# AnimatronicMouth.net
KiCad netlist of a schematic drawn in EAGLE
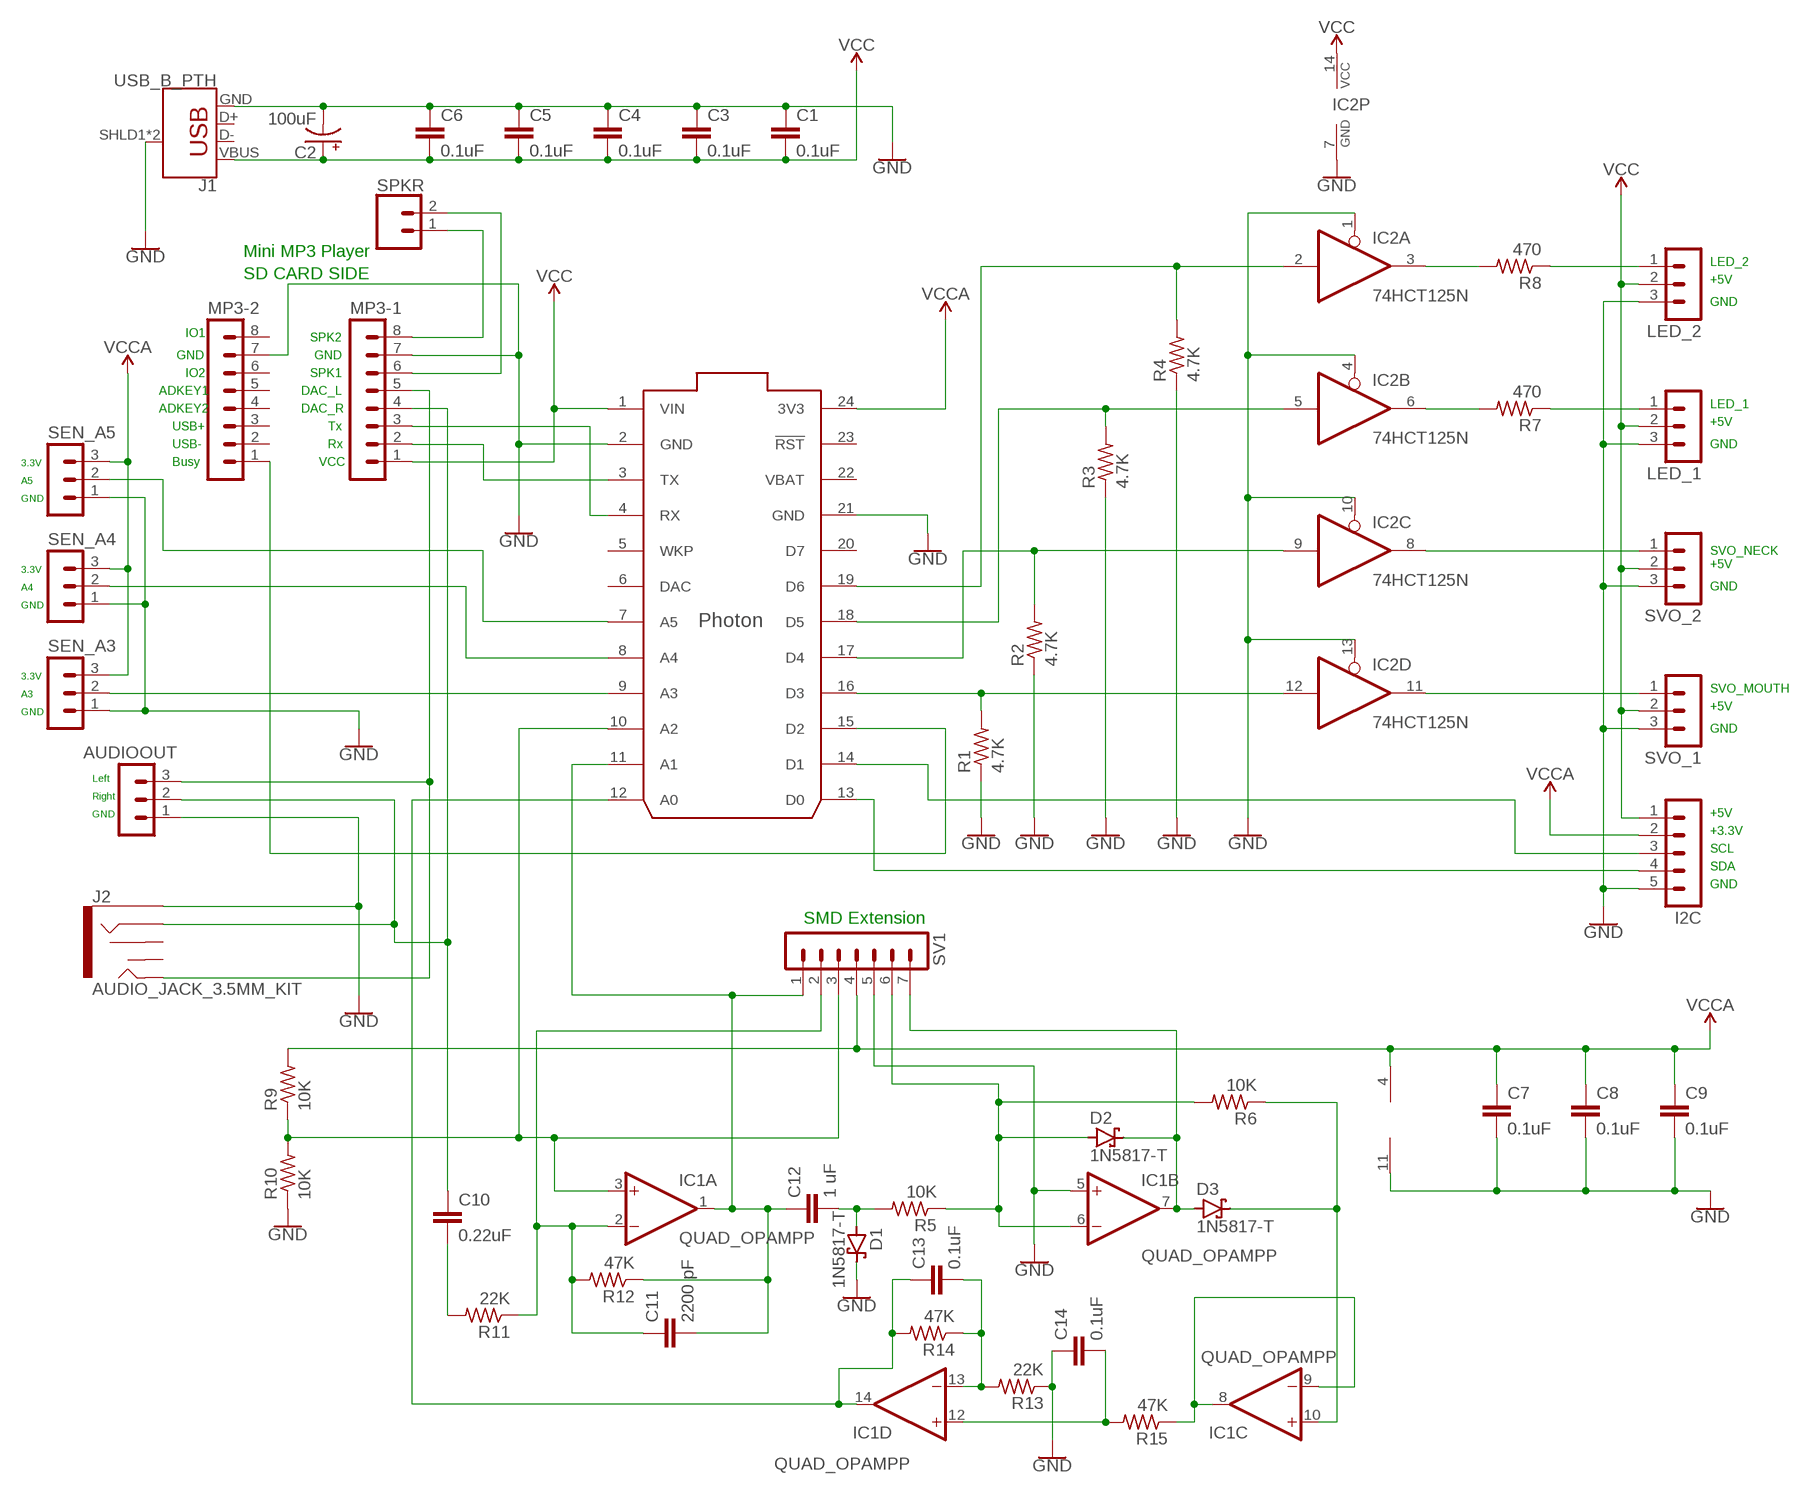
[diagram p0: schematic, sheet 1]

(export (version "E")
  (design (tool "Eeschema 10.0.6"))
  (components
    (comp (ref "AUDIOOUT")
      (value "MA03-1")
      (footprint "eagle-import:MA03-1")
      (libsource (lib "eagle-import") (part "MA03-1"))
    )
    (comp (ref "C1")
      (value "0.1uF")
      (footprint "eagle-import:CAP-PTH-SMALL-KIT")
      (libsource (lib "eagle-import") (part "0.1UF-KIT-EZ-50V-20%"))
    )
    (comp (ref "C2")
      (value "100uF")
      (footprint "eagle-import:CPOL-RADIAL-2.5MM-6.5MM")
      (libsource (lib "eagle-import") (part "100UF-POLAR-RADIAL-2.5MM-25V-20%"))
    )
    (comp (ref "C3")
      (value "0.1uF")
      (footprint "eagle-import:CAP-PTH-SMALL-KIT")
      (libsource (lib "eagle-import") (part "0.1UF-KIT-EZ-50V-20%"))
    )
    (comp (ref "C4")
      (value "0.1uF")
      (footprint "eagle-import:CAP-PTH-SMALL-KIT")
      (libsource (lib "eagle-import") (part "0.1UF-KIT-EZ-50V-20%"))
    )
    (comp (ref "C5")
      (value "0.1uF")
      (footprint "eagle-import:CAP-PTH-SMALL-KIT")
      (libsource (lib "eagle-import") (part "0.1UF-KIT-EZ-50V-20%"))
    )
    (comp (ref "C6")
      (value "0.1uF")
      (footprint "eagle-import:CAP-PTH-SMALL-KIT")
      (libsource (lib "eagle-import") (part "0.1UF-KIT-EZ-50V-20%"))
    )
    (comp (ref "C7")
      (value "0.1uF")
      (footprint "eagle-import:CAP-PTH-SMALL-KIT")
      (libsource (lib "eagle-import") (part "0.1UF-KIT-EZ-50V-20%"))
    )
    (comp (ref "C8")
      (value "0.1uF")
      (footprint "eagle-import:CAP-PTH-SMALL-KIT")
      (libsource (lib "eagle-import") (part "0.1UF-KIT-EZ-50V-20%"))
    )
    (comp (ref "C9")
      (value "0.1uF")
      (footprint "eagle-import:CAP-PTH-SMALL-KIT")
      (libsource (lib "eagle-import") (part "0.1UF-KIT-EZ-50V-20%"))
    )
    (comp (ref "C10")
      (value "0.22uF")
      (footprint "eagle-import:CAP-PTH-SMALL-KIT")
      (libsource (lib "eagle-import") (part "0.1UF-KIT-EZ-50V-20%"))
    )
    (comp (ref "C11")
      (value "2200 pF")
      (footprint "eagle-import:CAP-PTH-SMALL-KIT")
      (libsource (lib "eagle-import") (part "0.1UF-KIT-EZ-50V-20%"))
    )
    (comp (ref "C12")
      (value "1 uF")
      (footprint "eagle-import:CAP-PTH-SMALL-KIT")
      (libsource (lib "eagle-import") (part "0.1UF-KIT-EZ-50V-20%"))
    )
    (comp (ref "C13")
      (value "0.1uF")
      (footprint "eagle-import:CAP-PTH-SMALL-KIT")
      (libsource (lib "eagle-import") (part "0.1UF-KIT-EZ-50V-20%"))
    )
    (comp (ref "C14")
      (value "0.1uF")
      (footprint "eagle-import:CAP-PTH-SMALL-KIT")
      (libsource (lib "eagle-import") (part "0.1UF-KIT-EZ-50V-20%"))
    )
    (comp (ref "D1")
      (value "1N5817-T")
      (footprint "eagle-import:DO41-7.6")
      (libsource (lib "eagle-import") (part "1N5817-T"))
    )
    (comp (ref "D2")
      (value "1N5817-T")
      (footprint "eagle-import:DO41-7.6")
      (libsource (lib "eagle-import") (part "1N5817-T"))
    )
    (comp (ref "D3")
      (value "1N5817-T")
      (footprint "eagle-import:DO41-7.6")
      (libsource (lib "eagle-import") (part "1N5817-T"))
    )
    (comp (ref "I2C")
      (value "MA05-1")
      (footprint "eagle-import:MA05-1")
      (libsource (lib "eagle-import") (part "MA05-1"))
    )
    (comp (ref "IC1")
      (value "QUAD_OPAMPP")
      (footprint "eagle-import:DIL14")
      (libsource (lib "eagle-import") (part "QUAD_OPAMPP"))
    )
    (comp (ref "IC2")
      (value "74HCT125N")
      (footprint "eagle-import:DIL14")
      (libsource (lib "eagle-import") (part "74125NHCT"))
    )
    (comp (ref "J1")
      (value "USB_B_PTH")
      (footprint "eagle-import:USB-B-PTH")
      (libsource (lib "eagle-import") (part "USB_B_PTH"))
    )
    (comp (ref "J2")
      (value "AUDIO_JACK_3.5MM_KIT")
      (footprint "eagle-import:AUDIO-JACK-KIT")
      (libsource (lib "eagle-import") (part "AUDIO_JACK_3.5MM_KIT"))
    )
    (comp (ref "LED_1")
      (value "MA03-1")
      (footprint "eagle-import:MA03-1")
      (libsource (lib "eagle-import") (part "MA03-1"))
    )
    (comp (ref "LED_2")
      (value "MA03-1")
      (footprint "eagle-import:MA03-1")
      (libsource (lib "eagle-import") (part "MA03-1"))
    )
    (comp (ref "MP3-1")
      (value "MA08-1")
      (footprint "eagle-import:MA08-1")
      (libsource (lib "eagle-import") (part "MA08-1"))
    )
    (comp (ref "MP3-2")
      (value "MA08-1")
      (footprint "eagle-import:MA08-1")
      (libsource (lib "eagle-import") (part "MA08-1"))
    )
    (comp (ref "R1")
      (value "4.7K")
      (footprint "eagle-import:0309_12")
      (libsource (lib "eagle-import") (part "R-US_0309/12"))
    )
    (comp (ref "R2")
      (value "4.7K")
      (footprint "eagle-import:0309_12")
      (libsource (lib "eagle-import") (part "R-US_0309/12"))
    )
    (comp (ref "R3")
      (value "4.7K")
      (footprint "eagle-import:0309_12")
      (libsource (lib "eagle-import") (part "R-US_0309/12"))
    )
    (comp (ref "R4")
      (value "4.7K")
      (footprint "eagle-import:0309_12")
      (libsource (lib "eagle-import") (part "R-US_0309/12"))
    )
    (comp (ref "R5")
      (value "10K")
      (footprint "eagle-import:0309_12")
      (libsource (lib "eagle-import") (part "R-US_0309/12"))
    )
    (comp (ref "R6")
      (value "10K")
      (footprint "eagle-import:0309_12")
      (libsource (lib "eagle-import") (part "R-US_0309/12"))
    )
    (comp (ref "R7")
      (value "470")
      (footprint "eagle-import:0309_12")
      (libsource (lib "eagle-import") (part "R-US_0309/12"))
    )
    (comp (ref "R8")
      (value "470")
      (footprint "eagle-import:0309_12")
      (libsource (lib "eagle-import") (part "R-US_0309/12"))
    )
    (comp (ref "R9")
      (value "10K")
      (footprint "eagle-import:0309_12")
      (libsource (lib "eagle-import") (part "R-US_0309/12"))
    )
    (comp (ref "R10")
      (value "10K")
      (footprint "eagle-import:0309_12")
      (libsource (lib "eagle-import") (part "R-US_0309/12"))
    )
    (comp (ref "R11")
      (value "22K")
      (footprint "eagle-import:0309_12")
      (libsource (lib "eagle-import") (part "R-US_0309/12"))
    )
    (comp (ref "R12")
      (value "47K")
      (footprint "eagle-import:0309_12")
      (libsource (lib "eagle-import") (part "R-US_0309/12"))
    )
    (comp (ref "R13")
      (value "22K")
      (footprint "eagle-import:0309_12")
      (libsource (lib "eagle-import") (part "R-US_0309/12"))
    )
    (comp (ref "R14")
      (value "47K")
      (footprint "eagle-import:0309_12")
      (libsource (lib "eagle-import") (part "R-US_0309/12"))
    )
    (comp (ref "R15")
      (value "47K")
      (footprint "eagle-import:0309_12")
      (libsource (lib "eagle-import") (part "R-US_0309/12"))
    )
    (comp (ref "SEN_A3")
      (value "MA03-1")
      (footprint "eagle-import:MA03-1")
      (libsource (lib "eagle-import") (part "MA03-1"))
    )
    (comp (ref "SEN_A4")
      (value "MA03-1")
      (footprint "eagle-import:MA03-1")
      (libsource (lib "eagle-import") (part "MA03-1"))
    )
    (comp (ref "SEN_A5")
      (value "MA03-1")
      (footprint "eagle-import:MA03-1")
      (libsource (lib "eagle-import") (part "MA03-1"))
    )
    (comp (ref "SPKR")
      (value "CONN_023.5MM")
      (footprint "eagle-import:SCREWTERMINAL-3.5MM-2")
      (libsource (lib "eagle-import") (part "CONN_023.5MM"))
    )
    (comp (ref "SV1")
      (value "MA07-1")
      (footprint "eagle-import:MA07-1")
      (libsource (lib "eagle-import") (part "MA07-1"))
    )
    (comp (ref "SVO_1")
      (value "MA03-1")
      (footprint "eagle-import:MA03-1")
      (libsource (lib "eagle-import") (part "MA03-1"))
    )
    (comp (ref "SVO_2")
      (value "MA03-1")
      (footprint "eagle-import:MA03-1")
      (libsource (lib "eagle-import") (part "MA03-1"))
    )
    (comp (ref "U$1")
      (value "PHOTON_WITH_HEADERS")
      (footprint "eagle-import:PHOTON")
      (libsource (lib "eagle-import") (part "PHOTON_WITH_HEADERS"))
    )
  )
  (nets
    (net (code "1") (name "/VBAT") (class "Default")
      (node (ref "U$1") (pin "22") (pinfunction "VBAT_22") (pintype "power_in"))
    )
    (net (code "2") (name "GND") (class "Default")
      (node (ref "AUDIOOUT") (pin "1") (pinfunction "1_1") (pintype "passive"))
      (node (ref "C1") (pin "1") (pinfunction "1_1") (pintype "passive"))
      (node (ref "C14") (pin "1") (pinfunction "1_1") (pintype "passive"))
      (node (ref "C2") (pin "2") (pinfunction "-_2") (pintype "passive"))
      (node (ref "C3") (pin "1") (pinfunction "1_1") (pintype "passive"))
      (node (ref "C4") (pin "1") (pinfunction "1_1") (pintype "passive"))
      (node (ref "C5") (pin "1") (pinfunction "1_1") (pintype "passive"))
      (node (ref "C6") (pin "1") (pinfunction "1_1") (pintype "passive"))
      (node (ref "C7") (pin "2") (pinfunction "2_2") (pintype "passive"))
      (node (ref "C8") (pin "2") (pinfunction "2_2") (pintype "passive"))
      (node (ref "C9") (pin "2") (pinfunction "2_2") (pintype "passive"))
      (node (ref "D1") (pin "C") (pinfunction "C_C") (pintype "passive"))
      (node (ref "I2C") (pin "5") (pinfunction "5_5") (pintype "passive"))
      (node (ref "IC1") (pin "11") (pinfunction "V-_11") (pintype "power_in"))
      (node (ref "IC1") (pin "5") (pinfunction "+IN_5") (pintype "input"))
      (node (ref "IC2") (pin "1") (pinfunction "OE_1") (pintype "input"))
      (node (ref "IC2") (pin "10") (pinfunction "OE_10") (pintype "input"))
      (node (ref "IC2") (pin "13") (pinfunction "OE_13") (pintype "input"))
      (node (ref "IC2") (pin "4") (pinfunction "OE_4") (pintype "input"))
      (node (ref "IC2") (pin "7") (pinfunction "GND_7") (pintype "power_in"))
      (node (ref "J1") (pin "GND") (pinfunction "GND_GND") (pintype "power_in"))
      (node (ref "J1") (pin "SHLD1") (pinfunction "SHIELD_SHLD1") (pintype "bidirectional"))
      (node (ref "J1") (pin "SHLD2") (pinfunction "SHIELD_SHLD2") (pintype "bidirectional"))
      (node (ref "J2") (pin "SLEEVE") (pinfunction "SLEEVE_SLEEVE") (pintype "bidirectional"))
      (node (ref "LED_1") (pin "3") (pinfunction "3_3") (pintype "passive"))
      (node (ref "LED_2") (pin "3") (pinfunction "3_3") (pintype "passive"))
      (node (ref "MP3-1") (pin "7") (pinfunction "7_7") (pintype "passive"))
      (node (ref "MP3-2") (pin "7") (pinfunction "7_7") (pintype "passive"))
      (node (ref "R1") (pin "1") (pinfunction "1_1") (pintype "passive"))
      (node (ref "R10") (pin "1") (pinfunction "1_1") (pintype "passive"))
      (node (ref "R13") (pin "1") (pinfunction "1_1") (pintype "passive"))
      (node (ref "R2") (pin "1") (pinfunction "1_1") (pintype "passive"))
      (node (ref "R3") (pin "1") (pinfunction "1_1") (pintype "passive"))
      (node (ref "R4") (pin "1") (pinfunction "1_1") (pintype "passive"))
      (node (ref "SEN_A3") (pin "1") (pinfunction "1_1") (pintype "passive"))
      (node (ref "SEN_A4") (pin "1") (pinfunction "1_1") (pintype "passive"))
      (node (ref "SEN_A5") (pin "1") (pinfunction "1_1") (pintype "passive"))
      (node (ref "SV1") (pin "5") (pinfunction "5_5") (pintype "passive"))
      (node (ref "SVO_1") (pin "3") (pinfunction "3_3") (pintype "passive"))
      (node (ref "SVO_2") (pin "3") (pinfunction "3_3") (pintype "passive"))
      (node (ref "U$1") (pin "2") (pinfunction "GND_2") (pintype "power_in"))
      (node (ref "U$1") (pin "21") (pinfunction "GND_21") (pintype "power_in"))
    )
    (net (code "3") (name "Net-(AUDIOOUT-Pad2)") (class "Default")
      (node (ref "AUDIOOUT") (pin "2") (pinfunction "2_2") (pintype "passive"))
      (node (ref "C10") (pin "1") (pinfunction "1_1") (pintype "passive"))
      (node (ref "J2") (pin "RING") (pinfunction "RING_RING") (pintype "bidirectional"))
      (node (ref "MP3-1") (pin "4") (pinfunction "4_4") (pintype "passive"))
    )
    (net (code "4") (name "Net-(AUDIOOUT-Pad3)") (class "Default")
      (node (ref "AUDIOOUT") (pin "3") (pinfunction "3_3") (pintype "passive"))
      (node (ref "J2") (pin "TIP") (pinfunction "TIP_TIP") (pintype "bidirectional"))
      (node (ref "MP3-1") (pin "5") (pinfunction "5_5") (pintype "passive"))
    )
    (net (code "5") (name "Net-(C10-Pad2)") (class "Default")
      (node (ref "C10") (pin "2") (pinfunction "2_2") (pintype "passive"))
      (node (ref "R11") (pin "2") (pinfunction "2_2") (pintype "passive"))
    )
    (net (code "6") (name "Net-(C12-Pad2)") (class "Default")
      (node (ref "C12") (pin "2") (pinfunction "2_2") (pintype "passive"))
      (node (ref "D1") (pin "A") (pinfunction "A_A") (pintype "passive"))
      (node (ref "R5") (pin "2") (pinfunction "2_2") (pintype "passive"))
    )
    (net (code "7") (name "Net-(IC1A-+IN)") (class "Default")
      (node (ref "IC1") (pin "3") (pinfunction "+IN_3") (pintype "input"))
      (node (ref "R10") (pin "2") (pinfunction "2_2") (pintype "passive"))
      (node (ref "R9") (pin "1") (pinfunction "1_1") (pintype "passive"))
      (node (ref "SV1") (pin "3") (pinfunction "3_3") (pintype "passive"))
      (node (ref "U$1") (pin "10") (pinfunction "A2_10") (pintype "bidirectional"))
    )
    (net (code "8") (name "Net-(IC1A--IN)") (class "Default")
      (node (ref "C11") (pin "1") (pinfunction "1_1") (pintype "passive"))
      (node (ref "IC1") (pin "2") (pinfunction "-IN_2") (pintype "input"))
      (node (ref "R11") (pin "1") (pinfunction "1_1") (pintype "passive"))
      (node (ref "R12") (pin "2") (pinfunction "2_2") (pintype "passive"))
      (node (ref "SV1") (pin "2") (pinfunction "2_2") (pintype "passive"))
    )
    (net (code "9") (name "Net-(IC1A-OUT)") (class "Default")
      (node (ref "C11") (pin "2") (pinfunction "2_2") (pintype "passive"))
      (node (ref "C12") (pin "1") (pinfunction "1_1") (pintype "passive"))
      (node (ref "IC1") (pin "1") (pinfunction "OUT_1") (pintype "output"))
      (node (ref "R12") (pin "1") (pinfunction "1_1") (pintype "passive"))
      (node (ref "SV1") (pin "1") (pinfunction "1_1") (pintype "passive"))
      (node (ref "U$1") (pin "11") (pinfunction "A1_11") (pintype "bidirectional"))
    )
    (net (code "10") (name "Net-(IC1B--IN)") (class "Default")
      (node (ref "D2") (pin "A") (pinfunction "A_A") (pintype "passive"))
      (node (ref "IC1") (pin "6") (pinfunction "-IN_6") (pintype "input"))
      (node (ref "R5") (pin "1") (pinfunction "1_1") (pintype "passive"))
      (node (ref "R6") (pin "2") (pinfunction "2_2") (pintype "passive"))
      (node (ref "SV1") (pin "6") (pinfunction "6_6") (pintype "passive"))
    )
    (net (code "11") (name "Net-(IC1B-OUT)") (class "Default")
      (node (ref "D2") (pin "C") (pinfunction "C_C") (pintype "passive"))
      (node (ref "D3") (pin "A") (pinfunction "A_A") (pintype "passive"))
      (node (ref "IC1") (pin "7") (pinfunction "OUT_7") (pintype "output"))
      (node (ref "SV1") (pin "7") (pinfunction "7_7") (pintype "passive"))
    )
    (net (code "12") (name "Net-(IC1C-+IN)") (class "Default")
      (node (ref "D3") (pin "C") (pinfunction "C_C") (pintype "passive"))
      (node (ref "IC1") (pin "10") (pinfunction "+IN_10") (pintype "input"))
      (node (ref "R6") (pin "1") (pinfunction "1_1") (pintype "passive"))
    )
    (net (code "13") (name "Net-(IC1C--IN)") (class "Default")
      (node (ref "IC1") (pin "8") (pinfunction "OUT_8") (pintype "output"))
      (node (ref "IC1") (pin "9") (pinfunction "-IN_9") (pintype "input"))
      (node (ref "R15") (pin "1") (pinfunction "1_1") (pintype "passive"))
    )
    (net (code "14") (name "Net-(IC1D-+IN)") (class "Default")
      (node (ref "C14") (pin "2") (pinfunction "2_2") (pintype "passive"))
      (node (ref "IC1") (pin "12") (pinfunction "+IN_12") (pintype "input"))
      (node (ref "R15") (pin "2") (pinfunction "2_2") (pintype "passive"))
    )
    (net (code "15") (name "Net-(IC1D--IN)") (class "Default")
      (node (ref "C13") (pin "2") (pinfunction "2_2") (pintype "passive"))
      (node (ref "IC1") (pin "13") (pinfunction "-IN_13") (pintype "input"))
      (node (ref "R13") (pin "2") (pinfunction "2_2") (pintype "passive"))
      (node (ref "R14") (pin "1") (pinfunction "1_1") (pintype "passive"))
    )
    (net (code "16") (name "Net-(IC1D-OUT)") (class "Default")
      (node (ref "C13") (pin "1") (pinfunction "1_1") (pintype "passive"))
      (node (ref "IC1") (pin "14") (pinfunction "OUT_14") (pintype "output"))
      (node (ref "R14") (pin "2") (pinfunction "2_2") (pintype "passive"))
      (node (ref "U$1") (pin "12") (pinfunction "A0_12") (pintype "bidirectional"))
    )
    (net (code "17") (name "Net-(IC2A-I)") (class "Default")
      (node (ref "IC2") (pin "2") (pinfunction "I_2") (pintype "input"))
      (node (ref "R4") (pin "2") (pinfunction "2_2") (pintype "passive"))
      (node (ref "U$1") (pin "19") (pinfunction "D6_19") (pintype "bidirectional"))
    )
    (net (code "18") (name "Net-(IC2A-O)") (class "Default")
      (node (ref "IC2") (pin "3") (pinfunction "O_3") (pintype "tri_state"))
      (node (ref "R8") (pin "2") (pinfunction "2_2") (pintype "passive"))
    )
    (net (code "19") (name "Net-(IC2B-I)") (class "Default")
      (node (ref "IC2") (pin "5") (pinfunction "I_5") (pintype "input"))
      (node (ref "R3") (pin "2") (pinfunction "2_2") (pintype "passive"))
      (node (ref "U$1") (pin "18") (pinfunction "D5_18") (pintype "bidirectional"))
    )
    (net (code "20") (name "Net-(IC2B-O)") (class "Default")
      (node (ref "IC2") (pin "6") (pinfunction "O_6") (pintype "tri_state"))
      (node (ref "R7") (pin "2") (pinfunction "2_2") (pintype "passive"))
    )
    (net (code "21") (name "Net-(IC2C-I)") (class "Default")
      (node (ref "IC2") (pin "9") (pinfunction "I_9") (pintype "input"))
      (node (ref "R2") (pin "2") (pinfunction "2_2") (pintype "passive"))
      (node (ref "U$1") (pin "17") (pinfunction "D4_17") (pintype "bidirectional"))
    )
    (net (code "22") (name "Net-(IC2C-O)") (class "Default")
      (node (ref "IC2") (pin "8") (pinfunction "O_8") (pintype "tri_state"))
      (node (ref "SVO_2") (pin "1") (pinfunction "1_1") (pintype "passive"))
    )
    (net (code "23") (name "Net-(IC2D-I)") (class "Default")
      (node (ref "IC2") (pin "12") (pinfunction "I_12") (pintype "input"))
      (node (ref "R1") (pin "2") (pinfunction "2_2") (pintype "passive"))
      (node (ref "U$1") (pin "16") (pinfunction "D3_16") (pintype "bidirectional"))
    )
    (net (code "24") (name "Net-(IC2D-O)") (class "Default")
      (node (ref "IC2") (pin "11") (pinfunction "O_11") (pintype "tri_state"))
      (node (ref "SVO_1") (pin "1") (pinfunction "1_1") (pintype "passive"))
    )
    (net (code "25") (name "Net-(LED_1-Pad1)") (class "Default")
      (node (ref "LED_1") (pin "1") (pinfunction "1_1") (pintype "passive"))
      (node (ref "R7") (pin "1") (pinfunction "1_1") (pintype "passive"))
    )
    (net (code "26") (name "Net-(LED_2-Pad1)") (class "Default")
      (node (ref "LED_2") (pin "1") (pinfunction "1_1") (pintype "passive"))
      (node (ref "R8") (pin "1") (pinfunction "1_1") (pintype "passive"))
    )
    (net (code "27") (name "Net-(MP3-1-Pad6)") (class "Default")
      (node (ref "MP3-1") (pin "6") (pinfunction "6_6") (pintype "passive"))
      (node (ref "SPKR") (pin "2") (pinfunction "2_2") (pintype "passive"))
    )
    (net (code "28") (name "Net-(MP3-1-Pad8)") (class "Default")
      (node (ref "MP3-1") (pin "8") (pinfunction "8_8") (pintype "passive"))
      (node (ref "SPKR") (pin "1") (pinfunction "1_1") (pintype "passive"))
    )
    (net (code "29") (name "Net-(U$1-A3)") (class "Default")
      (node (ref "SEN_A3") (pin "2") (pinfunction "2_2") (pintype "passive"))
      (node (ref "U$1") (pin "9") (pinfunction "A3_9") (pintype "bidirectional"))
    )
    (net (code "30") (name "Net-(U$1-A4)") (class "Default")
      (node (ref "SEN_A4") (pin "2") (pinfunction "2_2") (pintype "passive"))
      (node (ref "U$1") (pin "8") (pinfunction "A4_8") (pintype "bidirectional"))
    )
    (net (code "31") (name "Net-(U$1-A5)") (class "Default")
      (node (ref "SEN_A5") (pin "2") (pinfunction "2_2") (pintype "passive"))
      (node (ref "U$1") (pin "7") (pinfunction "A5_7") (pintype "bidirectional"))
    )
    (net (code "32") (name "Net-(U$1-D0)") (class "Default")
      (node (ref "I2C") (pin "4") (pinfunction "4_4") (pintype "passive"))
      (node (ref "U$1") (pin "13") (pinfunction "D0_13") (pintype "bidirectional"))
    )
    (net (code "33") (name "Net-(U$1-D1)") (class "Default")
      (node (ref "I2C") (pin "3") (pinfunction "3_3") (pintype "passive"))
      (node (ref "U$1") (pin "14") (pinfunction "D1_14") (pintype "bidirectional"))
    )
    (net (code "34") (name "Net-(U$1-D2)") (class "Default")
      (node (ref "MP3-2") (pin "1") (pinfunction "1_1") (pintype "passive"))
      (node (ref "U$1") (pin "15") (pinfunction "D2_15") (pintype "bidirectional"))
    )
    (net (code "35") (name "Net-(U$1-RX)") (class "Default")
      (node (ref "MP3-1") (pin "3") (pinfunction "3_3") (pintype "passive"))
      (node (ref "U$1") (pin "4") (pinfunction "RX_4") (pintype "bidirectional"))
    )
    (net (code "36") (name "Net-(U$1-TX)") (class "Default")
      (node (ref "MP3-1") (pin "2") (pinfunction "2_2") (pintype "passive"))
      (node (ref "U$1") (pin "3") (pinfunction "TX_3") (pintype "bidirectional"))
    )
    (net (code "37") (name "VCC") (class "Default")
      (node (ref "C1") (pin "2") (pinfunction "2_2") (pintype "passive"))
      (node (ref "C2") (pin "1") (pinfunction "+_1") (pintype "passive"))
      (node (ref "C3") (pin "2") (pinfunction "2_2") (pintype "passive"))
      (node (ref "C4") (pin "2") (pinfunction "2_2") (pintype "passive"))
      (node (ref "C5") (pin "2") (pinfunction "2_2") (pintype "passive"))
      (node (ref "C6") (pin "2") (pinfunction "2_2") (pintype "passive"))
      (node (ref "I2C") (pin "1") (pinfunction "1_1") (pintype "passive"))
      (node (ref "IC2") (pin "14") (pinfunction "VCC_14") (pintype "power_in"))
      (node (ref "J1") (pin "VBUS") (pinfunction "VBUS_VBUS") (pintype "power_in"))
      (node (ref "LED_1") (pin "2") (pinfunction "2_2") (pintype "passive"))
      (node (ref "LED_2") (pin "2") (pinfunction "2_2") (pintype "passive"))
      (node (ref "MP3-1") (pin "1") (pinfunction "1_1") (pintype "passive"))
      (node (ref "SVO_1") (pin "2") (pinfunction "2_2") (pintype "passive"))
      (node (ref "SVO_2") (pin "2") (pinfunction "2_2") (pintype "passive"))
      (node (ref "U$1") (pin "1") (pinfunction "VIN_1") (pintype "power_in"))
    )
    (net (code "38") (name "VCCA") (class "Default")
      (node (ref "C7") (pin "1") (pinfunction "1_1") (pintype "passive"))
      (node (ref "C8") (pin "1") (pinfunction "1_1") (pintype "passive"))
      (node (ref "C9") (pin "1") (pinfunction "1_1") (pintype "passive"))
      (node (ref "I2C") (pin "2") (pinfunction "2_2") (pintype "passive"))
      (node (ref "IC1") (pin "4") (pinfunction "V+_4") (pintype "power_in"))
      (node (ref "R9") (pin "2") (pinfunction "2_2") (pintype "passive"))
      (node (ref "SEN_A3") (pin "3") (pinfunction "3_3") (pintype "passive"))
      (node (ref "SEN_A4") (pin "3") (pinfunction "3_3") (pintype "passive"))
      (node (ref "SEN_A5") (pin "3") (pinfunction "3_3") (pintype "passive"))
      (node (ref "SV1") (pin "4") (pinfunction "4_4") (pintype "passive"))
      (node (ref "U$1") (pin "24") (pinfunction "3V3_24") (pintype "power_in"))
    )
    (net (code "39") (name "unconnected-(J1-PadD+)") (class "Default")
      (node (ref "J1") (pin "D+") (pinfunction "D+_D+") (pintype "bidirectional"))
    )
    (net (code "40") (name "unconnected-(J1-PadD-)") (class "Default")
      (node (ref "J1") (pin "D-") (pinfunction "D-_D-") (pintype "bidirectional"))
    )
    (net (code "41") (name "unconnected-(J2-PadRSH)") (class "Default")
      (node (ref "J2") (pin "RSH") (pinfunction "RSH_RSH") (pintype "bidirectional"))
    )
    (net (code "42") (name "unconnected-(J2-PadTSH)") (class "Default")
      (node (ref "J2") (pin "TSH") (pinfunction "TSH_TSH") (pintype "bidirectional"))
    )
    (net (code "43") (name "unconnected-(MP3-2-Pad2)") (class "Default")
      (node (ref "MP3-2") (pin "2") (pinfunction "2_2") (pintype "passive"))
    )
    (net (code "44") (name "unconnected-(MP3-2-Pad3)") (class "Default")
      (node (ref "MP3-2") (pin "3") (pinfunction "3_3") (pintype "passive"))
    )
    (net (code "45") (name "unconnected-(MP3-2-Pad4)") (class "Default")
      (node (ref "MP3-2") (pin "4") (pinfunction "4_4") (pintype "passive"))
    )
    (net (code "46") (name "unconnected-(MP3-2-Pad5)") (class "Default")
      (node (ref "MP3-2") (pin "5") (pinfunction "5_5") (pintype "passive"))
    )
    (net (code "47") (name "unconnected-(MP3-2-Pad6)") (class "Default")
      (node (ref "MP3-2") (pin "6") (pinfunction "6_6") (pintype "passive"))
    )
    (net (code "48") (name "unconnected-(MP3-2-Pad8)") (class "Default")
      (node (ref "MP3-2") (pin "8") (pinfunction "8_8") (pintype "passive"))
    )
    (net (code "49") (name "unconnected-(U$1-D7-Pad20)") (class "Default")
      (node (ref "U$1") (pin "20") (pinfunction "D7_20") (pintype "bidirectional"))
    )
    (net (code "50") (name "unconnected-(U$1-DAC-Pad6)") (class "Default")
      (node (ref "U$1") (pin "6") (pinfunction "DAC_6") (pintype "bidirectional"))
    )
    (net (code "51") (name "unconnected-(U$1-WKP-Pad5)") (class "Default")
      (node (ref "U$1") (pin "5") (pinfunction "WKP_5") (pintype "bidirectional"))
    )
    (net (code "52") (name "unconnected-(U$1-~{RST}-Pad23)") (class "Default")
      (node (ref "U$1") (pin "23") (pinfunction "~{RST}_23") (pintype "bidirectional"))
    )
  )
)
